# Sheet1.net
KiCad netlist of a schematic drawn in Altium Designer
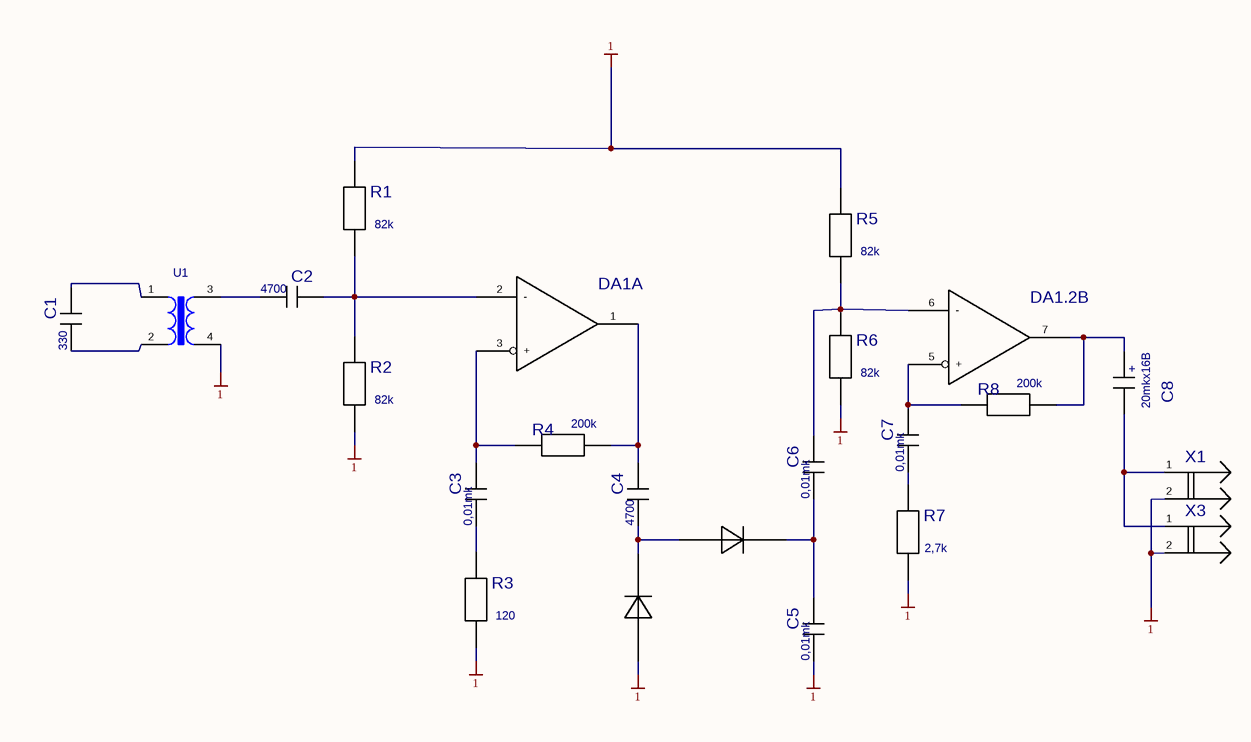
[diagram p0: Sheet1.SCHDOC]

(export (version "E")
  (design (tool "Eeschema 10.0.6"))
  (components
    (comp (ref "C1")
      (value "330")
      (footprint "CAP1")
      (description "CAP1")
      (libsource (lib "*") (part "CAP1"))
    )
    (comp (ref "C2")
      (value "4700")
      (footprint "CAP1")
      (description "CAP1")
      (libsource (lib "*") (part "CAP1"))
    )
    (comp (ref "C3")
      (value "0,01mk")
      (footprint "CAP1")
      (description "CAP1")
      (libsource (lib "*") (part "CAP1"))
    )
    (comp (ref "C4")
      (value "4700")
      (footprint "CAP1")
      (description "CAP1")
      (libsource (lib "*") (part "CAP1"))
    )
    (comp (ref "C5")
      (value "0,01mk")
      (footprint "CAP1")
      (description "CAP1")
      (libsource (lib "*") (part "CAP1"))
    )
    (comp (ref "C6")
      (value "0,01mk")
      (footprint "CAP1")
      (description "CAP1")
      (libsource (lib "*") (part "CAP1"))
    )
    (comp (ref "C7")
      (value "0,01mk")
      (footprint "CAP1")
      (description "CAP1")
      (libsource (lib "*") (part "CAP1"))
    )
    (comp (ref "C8")
      (value "20mkx16B")
      (footprint "CAP2")
      (description "CAP2")
      (libsource (lib "*") (part "CAP2"))
    )
    (comp (ref "DA1") (value "LM358") (libsource (lib "*") (part "LM358")))
    (comp (ref "DA1.2") (value "LM358") (description "LM358_VARIANT_1") (libsource (lib "*") (part "LM358")))
    (comp (ref "R1") (value "82k") (footprint "RES") (description "RES") (libsource (lib "*") (part "RES")))
    (comp (ref "R2") (value "82k") (footprint "RES") (description "RES") (libsource (lib "*") (part "RES")))
    (comp (ref "R3") (value "120") (footprint "RES") (description "RES") (libsource (lib "*") (part "RES")))
    (comp (ref "R4") (value "200k") (footprint "RES") (description "RES") (libsource (lib "*") (part "RES")))
    (comp (ref "R5") (value "82k") (footprint "RES") (description "RES") (libsource (lib "*") (part "RES")))
    (comp (ref "R6") (value "82k") (footprint "RES") (description "RES") (libsource (lib "*") (part "RES")))
    (comp (ref "R7") (value "2,7k") (footprint "RES") (description "RES") (libsource (lib "*") (part "RES")))
    (comp (ref "R8") (value "200k") (footprint "RES") (description "RES") (libsource (lib "*") (part "RES")))
    (comp (ref "U1") (value "TR") (libsource (lib "*") (part "TR")))
    (comp (ref "VD1") (value "КД209") (footprint "DO-7") (libsource (lib "*") (part "КД209")))
    (comp (ref "VD2") (value "КД209") (footprint "DO-7") (libsource (lib "*") (part "КД209")))
    (comp (ref "X1") (value "2XR") (footprint "2XR") (libsource (lib "*") (part "2XR")))
    (comp (ref "X3") (value "2XR") (footprint "2XR") (libsource (lib "*") (part "2XR")))
  )
  (nets
    (net (code "1") (name "1") (class "Default")
      (node (ref "C5") (pin "1") (pinfunction "1_1") (pintype "passive"))
      (node (ref "R1") (pin "2") (pinfunction "2_2") (pintype "passive"))
      (node (ref "R2") (pin "1") (pinfunction "1_1") (pintype "passive"))
      (node (ref "R3") (pin "1") (pinfunction "1_1") (pintype "passive"))
      (node (ref "R5") (pin "2") (pinfunction "2_2") (pintype "passive"))
      (node (ref "R6") (pin "1") (pinfunction "1_1") (pintype "passive"))
      (node (ref "R7") (pin "1") (pinfunction "1_1") (pintype "passive"))
      (node (ref "U1") (pin "4") (pinfunction "3_4") (pintype "passive"))
      (node (ref "VD1") (pin "2") (pinfunction "A_2") (pintype "passive"))
      (node (ref "X1") (pin "2") (pinfunction "I/O2_2") (pintype "passive"))
      (node (ref "X3") (pin "2") (pinfunction "I/O2_2") (pintype "passive"))
    )
    (net (code "2") (name "GND") (class "Default")
      (node (ref "DA1") (pin "4") (pinfunction "GND_4") (pintype "power_in"))
      (node (ref "DA1.2") (pin "4") (pinfunction "GND_4") (pintype "power_in"))
    )
    (net (code "3") (name "Net-(C3-Pad1)") (class "Default")
      (node (ref "C3") (pin "1") (pinfunction "1_1") (pintype "passive"))
      (node (ref "R3") (pin "2") (pinfunction "2_2") (pintype "passive"))
    )
    (net (code "4") (name "Net-(C7-Pad1)") (class "Default")
      (node (ref "C7") (pin "1") (pinfunction "1_1") (pintype "passive"))
      (node (ref "R7") (pin "2") (pinfunction "2_2") (pintype "passive"))
    )
    (net (code "5") (name "Net-(DA1.2B-+)") (class "Default")
      (node (ref "C7") (pin "2") (pinfunction "2_2") (pintype "passive"))
      (node (ref "DA1.2") (pin "5") (pinfunction "+_5") (pintype "passive"))
      (node (ref "R8") (pin "2") (pinfunction "2_2") (pintype "passive"))
    )
    (net (code "6") (name "Net-(DA1.2B--)") (class "Default")
      (node (ref "C6") (pin "2") (pinfunction "2_2") (pintype "passive"))
      (node (ref "DA1.2") (pin "6") (pinfunction "-_6") (pintype "passive"))
      (node (ref "R5") (pin "1") (pinfunction "1_1") (pintype "passive"))
      (node (ref "R6") (pin "2") (pinfunction "2_2") (pintype "passive"))
    )
    (net (code "7") (name "Net-(DA1.2B-OUT)") (class "Default")
      (node (ref "C8") (pin "1") (pinfunction "1_1") (pintype "passive"))
      (node (ref "DA1.2") (pin "7") (pinfunction "OUT_7") (pintype "passive"))
      (node (ref "R8") (pin "1") (pinfunction "1_1") (pintype "passive"))
    )
    (net (code "8") (name "Net-(DA1A-+)") (class "Default")
      (node (ref "C3") (pin "2") (pinfunction "2_2") (pintype "passive"))
      (node (ref "DA1") (pin "3") (pinfunction "+_3") (pintype "passive"))
      (node (ref "R4") (pin "2") (pinfunction "2_2") (pintype "passive"))
    )
    (net (code "9") (name "Net-(DA1A--)") (class "Default")
      (node (ref "C2") (pin "2") (pinfunction "2_2") (pintype "passive"))
      (node (ref "DA1") (pin "2") (pinfunction "-_2") (pintype "passive"))
      (node (ref "R1") (pin "1") (pinfunction "1_1") (pintype "passive"))
      (node (ref "R2") (pin "2") (pinfunction "2_2") (pintype "passive"))
    )
    (net (code "10") (name "Net-(DA1A-OUT)") (class "Default")
      (node (ref "C4") (pin "2") (pinfunction "2_2") (pintype "passive"))
      (node (ref "DA1") (pin "1") (pinfunction "OUT_1") (pintype "passive"))
      (node (ref "R4") (pin "1") (pinfunction "1_1") (pintype "passive"))
    )
    (net (code "11") (name "Net-(U1-0)") (class "Default")
      (node (ref "C1") (pin "2") (pinfunction "2_2") (pintype "passive"))
      (node (ref "U1") (pin "1") (pinfunction "0_1") (pintype "passive"))
    )
    (net (code "12") (name "Net-(U1-1)") (class "Default")
      (node (ref "C1") (pin "1") (pinfunction "1_1") (pintype "passive"))
      (node (ref "U1") (pin "2") (pinfunction "1_2") (pintype "passive"))
    )
    (net (code "13") (name "Net-(U1-2)") (class "Default")
      (node (ref "C2") (pin "1") (pinfunction "1_1") (pintype "passive"))
      (node (ref "U1") (pin "3") (pinfunction "2_3") (pintype "passive"))
    )
    (net (code "14") (name "Net-(VD1-K)") (class "Default")
      (node (ref "C4") (pin "1") (pinfunction "1_1") (pintype "passive"))
      (node (ref "VD1") (pin "1") (pinfunction "K_1") (pintype "passive"))
      (node (ref "VD2") (pin "2") (pinfunction "A_2") (pintype "passive"))
    )
    (net (code "15") (name "Net-(VD2-K)") (class "Default")
      (node (ref "C5") (pin "2") (pinfunction "2_2") (pintype "passive"))
      (node (ref "C6") (pin "1") (pinfunction "1_1") (pintype "passive"))
      (node (ref "VD2") (pin "1") (pinfunction "K_1") (pintype "passive"))
    )
    (net (code "16") (name "Net-(X1-I{slash}O1)") (class "Default")
      (node (ref "C8") (pin "2") (pinfunction "2_2") (pintype "passive"))
      (node (ref "X1") (pin "1") (pinfunction "I/O1_1") (pintype "passive"))
      (node (ref "X3") (pin "1") (pinfunction "I/O1_1") (pintype "passive"))
    )
    (net (code "17") (name "VCC") (class "Default")
      (node (ref "DA1") (pin "8") (pinfunction "VCC_8") (pintype "power_in"))
      (node (ref "DA1.2") (pin "8") (pinfunction "VCC_8") (pintype "power_in"))
    )
  )
)
